# fish_V1_1.net
KiCad netlist of a schematic drawn in Altium Designer
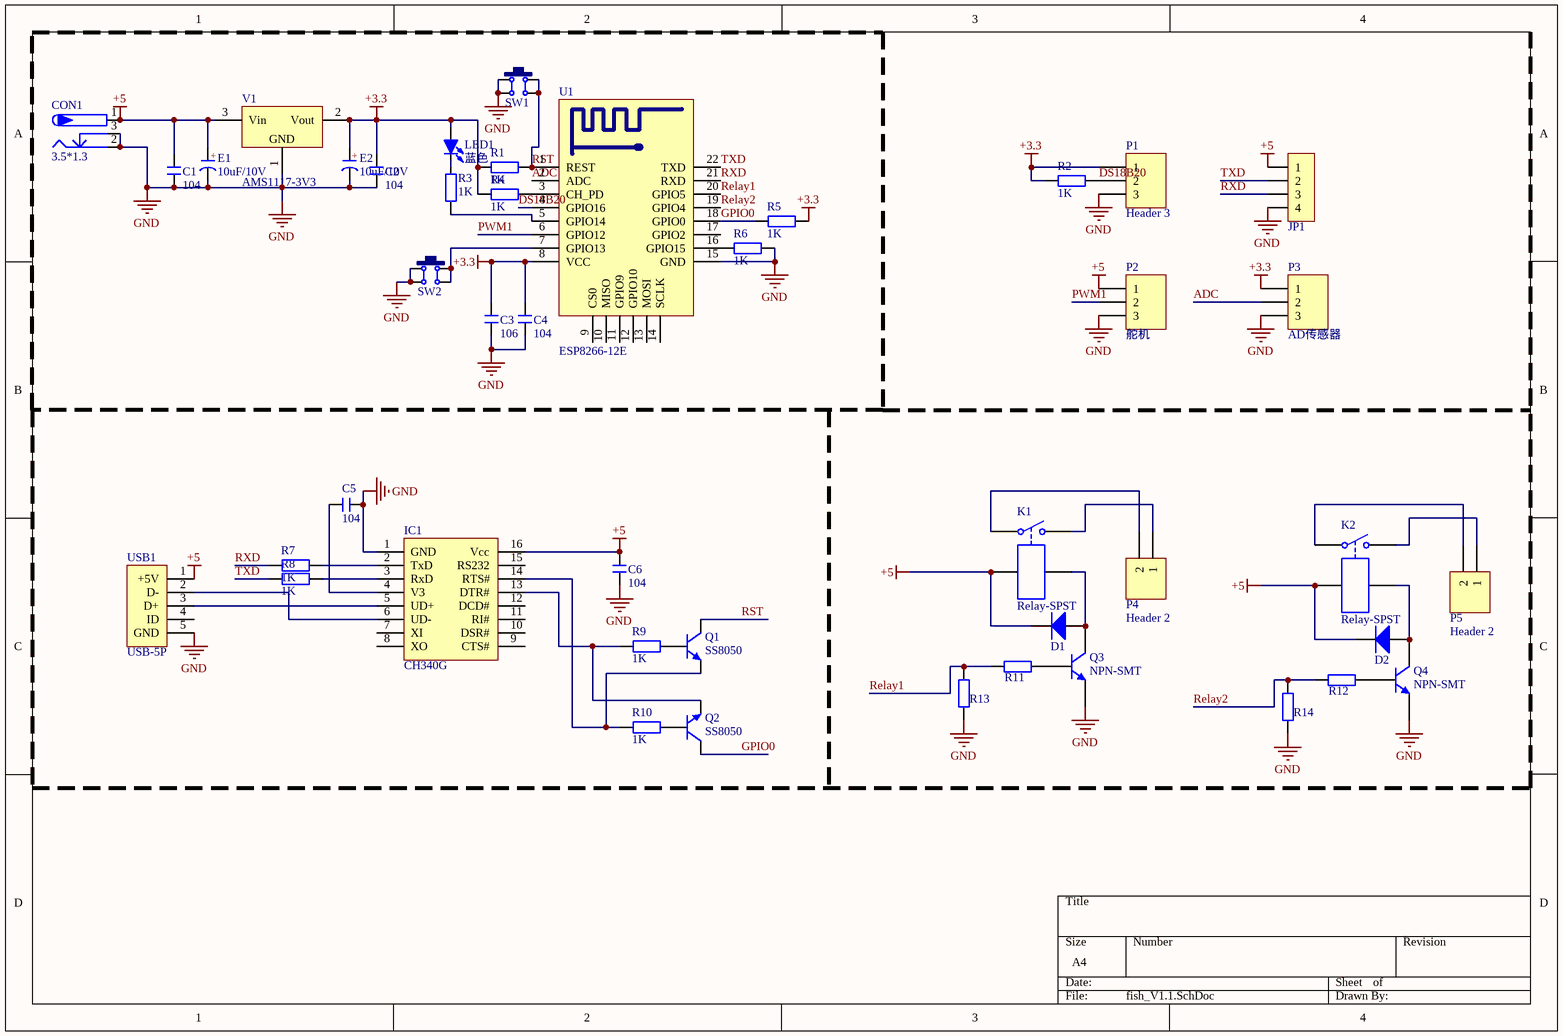
[diagram p0: fish_V1.1.SchDoc]

(export (version "E")
  (design (tool "Eeschema 10.0.6"))
  (components
    (comp (ref "C1")
      (value "104")
      (footprint "C 0603")
      (description "无极性贴片电容")
      (fields (field (name "版权归属") "黎明电子style"))
      (libsource (lib "电阻-电容-电感") (part "C"))
    )
    (comp (ref "C2")
      (value "104")
      (footprint "C 0603")
      (description "无极性贴片电容")
      (fields (field (name "版权归属") "黎明电子style"))
      (libsource (lib "电阻-电容-电感") (part "C"))
    )
    (comp (ref "C3")
      (value "106")
      (footprint "C 0603")
      (description "无极性贴片电容")
      (fields (field (name "版权归属") "黎明电子style"))
      (libsource (lib "电阻-电容-电感") (part "C"))
    )
    (comp (ref "C4")
      (value "104")
      (footprint "C 0603")
      (description "无极性贴片电容")
      (fields (field (name "版权归属") "黎明电子style"))
      (libsource (lib "电阻-电容-电感") (part "C"))
    )
    (comp (ref "C5")
      (value "104")
      (footprint "C 0603")
      (description "无极性贴片电容")
      (fields (field (name "版权归属") "黎明电子style"))
      (libsource (lib "电阻-电容-电感") (part "C"))
    )
    (comp (ref "C6")
      (value "104")
      (footprint "C 0603")
      (description "无极性贴片电容")
      (fields (field (name "版权归属") "黎明电子style"))
      (libsource (lib "电阻-电容-电感") (part "C"))
    )
    (comp (ref "CON1")
      (value "3.5*1.3")
      (footprint "DC-005")
      (description "低压电源接口")
      (fields (field (name "版权归属") "黎明电子style"))
      (libsource (lib "接口类") (part "P-DC"))
    )
    (comp (ref "D1")
      (value "Diode  Glass")
      (footprint "DSO-C2/X2.3")
      (description "High Conductance Fast Diode")
      (fields (field (name "PUBLISHER") "Altium Limited"))
      (libsource (lib "(NEW)DRC_MD Library") (part "Diode  Glass"))
    )
    (comp (ref "D2")
      (value "Diode  Glass")
      (footprint "DSO-C2/X2.3")
      (description "High Conductance Fast Diode")
      (fields (field (name "PUBLISHER") "Altium Limited"))
      (libsource (lib "(NEW)DRC_MD Library") (part "Diode  Glass"))
    )
    (comp (ref "E1")
      (value "10uF/10V")
      (footprint "CM D(6.3*5.4)")
      (description "贴片电解电容")
      (fields (field (name "版权归属") "黎明电子style"))
      (libsource (lib "电阻-电容-电感") (part "C-CM"))
    )
    (comp (ref "E2")
      (value "10uF/10V")
      (footprint "CM D(6.3*5.4)")
      (description "贴片电解电容")
      (fields (field (name "版权归属") "黎明电子style"))
      (libsource (lib "电阻-电容-电感") (part "C-CM"))
    )
    (comp (ref "IC1")
      (value "CH340G")
      (footprint "SOP16_L")
      (description "串口转USB")
      (fields (field (name "版权归属") "黎明电子style"))
      (libsource (lib "IC芯片") (part "CH340G"))
    )
    (comp (ref "JP1")
      (value "HDR-1X4")
      (footprint "XH2.54-4P")
      (description "4P接插件")
      (fields (field (name "版权归属") "黎明电子style"))
      (libsource (lib "接插件") (part "Header 4"))
    )
    (comp (ref "K1")
      (value "Relay-SPST")
      (footprint "RELAY_HF46F")
      (description "Single-Pole Single-Throw Relay")
      (fields (field (name "PUBLISHER") "Altium Limited"))
      (libsource (lib "(NEW)DRC_MD Library") (part "Relay-SPST"))
    )
    (comp (ref "K2")
      (value "Relay-SPST")
      (footprint "RELAY_HF46F")
      (description "Single-Pole Single-Throw Relay")
      (fields (field (name "PUBLISHER") "Altium Limited"))
      (libsource (lib "(NEW)DRC_MD Library") (part "Relay-SPST"))
    )
    (comp (ref "LED1")
      (value "蓝色")
      (footprint "LED 3MM-B")
      (description "插件LED")
      (fields (field (name "版权归属") "黎明电子style"))
      (libsource (lib "LED") (part "LED-3MM"))
    )
    (comp (ref "P1")
      (value "Header 3")
      (footprint "HX2.54-3")
      (description "Header, 3-Pin")
      (fields (field (name "PUBLISHER") "Altium Limited"))
      (libsource (lib "(NEW)DRC_MD Library") (part "Header 3"))
    )
    (comp (ref "P2")
      (value "舵机")
      (footprint "HX2.54-3")
      (description "Header, 3-Pin")
      (fields (field (name "PUBLISHER") "Altium Limited"))
      (libsource (lib "(NEW)DRC_MD Library") (part "Header 3"))
    )
    (comp (ref "P3")
      (value "AD传感器")
      (footprint "HX2.54-3")
      (description "Header, 3-Pin")
      (fields (field (name "PUBLISHER") "Altium Limited"))
      (libsource (lib "(NEW)DRC_MD Library") (part "Header 3"))
    )
    (comp (ref "P4")
      (value "Header 2")
      (footprint "HX5.08-2L")
      (description "Header, 2-Pin")
      (fields (field (name "PUBLISHER") "Altium Limited"))
      (libsource (lib "(NEW)DRC_MD Library") (part "Header 2"))
    )
    (comp (ref "P5")
      (value "Header 2")
      (footprint "HX5.08-2L")
      (description "Header, 2-Pin")
      (fields (field (name "PUBLISHER") "Altium Limited"))
      (libsource (lib "(NEW)DRC_MD Library") (part "Header 2"))
    )
    (comp (ref "Q1")
      (value "SS8050")
      (footprint "SOT23-3N")
      (description "高频放大-NPN型")
      (fields (field (name "版权归属") "黎明电子style"))
      (libsource (lib "三极管") (part "8050-SMD"))
    )
    (comp (ref "Q2")
      (value "SS8050")
      (footprint "SOT23-3N")
      (description "高频放大-NPN型")
      (fields (field (name "版权归属") "黎明电子style"))
      (libsource (lib "三极管") (part "8050-SMD"))
    )
    (comp (ref "Q3")
      (value "NPN-SMT")
      (footprint "SOT-23")
      (description "NPN Bipolar Transistor")
      (fields (field (name "PUBLISHER") "Altium Limited"))
      (libsource (lib "(NEW)DRC_MD Library") (part "NPN-SMT"))
    )
    (comp (ref "Q4")
      (value "NPN-SMT")
      (footprint "SOT-23")
      (description "NPN Bipolar Transistor")
      (fields (field (name "PUBLISHER") "Altium Limited"))
      (libsource (lib "(NEW)DRC_MD Library") (part "NPN-SMT"))
    )
    (comp (ref "R1")
      (value "1K")
      (footprint "R 0603")
      (description "贴片电阻")
      (fields (field (name "版权归属") "黎明电子style"))
      (libsource (lib "电阻-电容-电感") (part "R"))
    )
    (comp (ref "R2")
      (value "1K")
      (footprint "R 0603")
      (description "贴片电阻")
      (fields (field (name "版权归属") "黎明电子style"))
      (libsource (lib "电阻-电容-电感") (part "R"))
    )
    (comp (ref "R3")
      (value "1K")
      (footprint "R 0603")
      (description "贴片电阻")
      (fields (field (name "版权归属") "黎明电子style"))
      (libsource (lib "电阻-电容-电感") (part "R"))
    )
    (comp (ref "R4")
      (value "1K")
      (footprint "R 0603")
      (description "贴片电阻")
      (fields (field (name "版权归属") "黎明电子style"))
      (libsource (lib "电阻-电容-电感") (part "R"))
    )
    (comp (ref "R5")
      (value "1K")
      (footprint "R 0603")
      (description "贴片电阻")
      (fields (field (name "版权归属") "黎明电子style"))
      (libsource (lib "电阻-电容-电感") (part "R"))
    )
    (comp (ref "R6")
      (value "1K")
      (footprint "R 0603")
      (description "贴片电阻")
      (fields (field (name "版权归属") "黎明电子style"))
      (libsource (lib "电阻-电容-电感") (part "R"))
    )
    (comp (ref "R7")
      (value "1K")
      (footprint "R 0603")
      (description "贴片电阻")
      (fields (field (name "版权归属") "黎明电子style"))
      (libsource (lib "电阻-电容-电感") (part "R"))
    )
    (comp (ref "R8")
      (value "1K")
      (footprint "R 0603")
      (description "贴片电阻")
      (fields (field (name "版权归属") "黎明电子style"))
      (libsource (lib "电阻-电容-电感") (part "R"))
    )
    (comp (ref "R9")
      (value "1K")
      (footprint "R 0603")
      (description "贴片电阻")
      (fields (field (name "版权归属") "黎明电子style"))
      (libsource (lib "电阻-电容-电感") (part "R"))
    )
    (comp (ref "R10")
      (value "1K")
      (footprint "R 0603")
      (description "贴片电阻")
      (fields (field (name "版权归属") "黎明电子style"))
      (libsource (lib "电阻-电容-电感") (part "R"))
    )
    (comp (ref "R11")
      (value "Resistor Chip")
      (footprint "RES_0603")
      (description "Resistor")
      (fields (field (name "PUBLISHER") "Altium Limited"))
      (libsource (lib "(NEW)DRC_MD Library") (part "Resistor Chip"))
    )
    (comp (ref "R12")
      (value "Resistor Chip")
      (footprint "RES_0603")
      (description "Resistor")
      (fields (field (name "PUBLISHER") "Altium Limited"))
      (libsource (lib "(NEW)DRC_MD Library") (part "Resistor Chip"))
    )
    (comp (ref "R13")
      (value "Resistor Chip")
      (footprint "RES_0603")
      (description "Resistor")
      (fields (field (name "PUBLISHER") "Altium Limited"))
      (libsource (lib "") (part "Resistor Chip_1"))
    )
    (comp (ref "R14")
      (value "Resistor Chip")
      (footprint "RES_0603")
      (description "Resistor")
      (fields (field (name "PUBLISHER") "Altium Limited"))
      (libsource (lib "") (part "Resistor Chip_1"))
    )
    (comp (ref "SW1")
      (value "6x6x5")
      (footprint "TSW SMD-6*6*4.3")
      (description "贴片6x6轻触开关")
      (fields (field (name "版权归属") "黎明电子style"))
      (libsource (lib "按键-开关") (part "TSW SMD-6x6"))
    )
    (comp (ref "SW2")
      (value "6x6x5")
      (footprint "TSW SMD-6*6*4.3")
      (description "贴片6x6轻触开关")
      (fields (field (name "版权归属") "黎明电子style"))
      (libsource (lib "按键-开关") (part "TSW SMD-6x6"))
    )
    (comp (ref "U1")
      (value "ESP8266-12E")
      (footprint "ESP_12E")
      (description "串口 WIFI模块，ESP-12E")
      (fields (field (name "版权归属") "黎明电子style"))
      (libsource (lib "模块") (part "ESP8266-12E"))
    )
    (comp (ref "USB1")
      (value "USB-5P")
      (footprint "USB-MICRO_D")
      (description "微型USB母座")
      (fields (field (name "版权归属") "黎明电子style"))
      (libsource (lib "接口类") (part "USB-5P"))
    )
    (comp (ref "V1")
      (value "AMS1117-3V3")
      (footprint "SOT223_L")
      (description "三端稳压芯片")
      (fields (field (name "版权归属") "黎明电子style"))
      (libsource (lib "IC芯片") (part "AMS1117"))
    )
  )
  (nets
    (net (code "1") (name "+3.3") (class "Default")
      (node (ref "C2") (pin "2") (pinfunction "2_2") (pintype "passive"))
      (node (ref "C3") (pin "2") (pinfunction "2_2") (pintype "passive"))
      (node (ref "C4") (pin "2") (pinfunction "2_2") (pintype "passive"))
      (node (ref "E2") (pin "1") (pinfunction "A_1") (pintype "passive"))
      (node (ref "LED1") (pin "1") (pinfunction "A_1") (pintype "passive"))
      (node (ref "P1") (pin "1") (pinfunction "1_1") (pintype "passive"))
      (node (ref "P3") (pin "1") (pinfunction "1_1") (pintype "passive"))
      (node (ref "R1") (pin "1") (pinfunction "1_1") (pintype "passive"))
      (node (ref "R2") (pin "1") (pinfunction "1_1") (pintype "passive"))
      (node (ref "R4") (pin "1") (pinfunction "1_1") (pintype "passive"))
      (node (ref "R5") (pin "2") (pinfunction "2_2") (pintype "passive"))
      (node (ref "U1") (pin "8") (pinfunction "VCC_8") (pintype "passive"))
      (node (ref "V1") (pin "2") (pinfunction "Vout_2") (pintype "passive"))
    )
    (net (code "2") (name "+5") (class "Default")
      (node (ref "C1") (pin "2") (pinfunction "2_2") (pintype "passive"))
      (node (ref "C6") (pin "2") (pinfunction "2_2") (pintype "passive"))
      (node (ref "CON1") (pin "1") (pintype "power_in"))
      (node (ref "D1") (pin "2") (pinfunction "K_2") (pintype "passive"))
      (node (ref "D2") (pin "2") (pinfunction "K_2") (pintype "passive"))
      (node (ref "E1") (pin "1") (pinfunction "A_1") (pintype "passive"))
      (node (ref "IC1") (pin "16") (pinfunction "Vcc_16") (pintype "passive"))
      (node (ref "JP1") (pin "1") (pinfunction "1_1") (pintype "passive"))
      (node (ref "K1") (pin "3") (pinfunction "3_3") (pintype "passive"))
      (node (ref "K2") (pin "3") (pinfunction "3_3") (pintype "passive"))
      (node (ref "P2") (pin "1") (pinfunction "1_1") (pintype "passive"))
      (node (ref "USB1") (pin "1") (pinfunction "+5V_1") (pintype "passive"))
      (node (ref "V1") (pin "3") (pinfunction "Vin_3") (pintype "passive"))
    )
    (net (code "3") (name "/ADC") (class "Default")
      (node (ref "P3") (pin "2") (pinfunction "2_2") (pintype "passive"))
      (node (ref "U1") (pin "2") (pinfunction "ADC_2") (pintype "passive"))
    )
    (net (code "4") (name "/DS18B20") (class "Default")
      (node (ref "P1") (pin "2") (pinfunction "2_2") (pintype "passive"))
      (node (ref "R2") (pin "2") (pinfunction "2_2") (pintype "passive"))
      (node (ref "U1") (pin "4") (pinfunction "GPIO16_4") (pintype "passive"))
    )
    (net (code "5") (name "/GPIO0") (class "Default")
      (node (ref "Q2") (pin "3") (pinfunction "C_3") (pintype "passive"))
      (node (ref "R5") (pin "1") (pinfunction "1_1") (pintype "passive"))
      (node (ref "U1") (pin "18") (pinfunction "GPIO0_18") (pintype "passive"))
    )
    (net (code "6") (name "/PWM1") (class "Default")
      (node (ref "P2") (pin "2") (pinfunction "2_2") (pintype "passive"))
      (node (ref "U1") (pin "6") (pinfunction "GPIO12_6") (pintype "passive"))
    )
    (net (code "7") (name "/RST") (class "Default")
      (node (ref "Q1") (pin "3") (pinfunction "C_3") (pintype "passive"))
      (node (ref "R1") (pin "2") (pinfunction "2_2") (pintype "passive"))
      (node (ref "SW1") (pin "2") (pinfunction "2_2") (pintype "passive"))
      (node (ref "SW1") (pin "3") (pinfunction "3_3") (pintype "passive"))
      (node (ref "U1") (pin "1") (pinfunction "REST_1") (pintype "passive"))
    )
    (net (code "8") (name "/RXD") (class "Default")
      (node (ref "JP1") (pin "3") (pinfunction "3_3") (pintype "passive"))
      (node (ref "R7") (pin "1") (pinfunction "1_1") (pintype "passive"))
      (node (ref "U1") (pin "21") (pinfunction "RXD_21") (pintype "passive"))
    )
    (net (code "9") (name "/Relay1") (class "Default")
      (node (ref "R11") (pin "2") (pinfunction "2_2") (pintype "passive"))
      (node (ref "R13") (pin "2") (pinfunction "2_2") (pintype "passive"))
      (node (ref "U1") (pin "20") (pinfunction "GPIO5_20") (pintype "passive"))
    )
    (net (code "10") (name "/Relay2") (class "Default")
      (node (ref "R12") (pin "2") (pinfunction "2_2") (pintype "passive"))
      (node (ref "R14") (pin "2") (pinfunction "2_2") (pintype "passive"))
      (node (ref "U1") (pin "19") (pinfunction "GPIO4_19") (pintype "passive"))
    )
    (net (code "11") (name "/TXD") (class "Default")
      (node (ref "JP1") (pin "2") (pinfunction "2_2") (pintype "passive"))
      (node (ref "R8") (pin "1") (pinfunction "1_1") (pintype "passive"))
      (node (ref "U1") (pin "22") (pinfunction "TXD_22") (pintype "passive"))
    )
    (net (code "12") (name "GND") (class "Default")
      (node (ref "C1") (pin "1") (pinfunction "1_1") (pintype "passive"))
      (node (ref "C2") (pin "1") (pinfunction "1_1") (pintype "passive"))
      (node (ref "C3") (pin "1") (pinfunction "1_1") (pintype "passive"))
      (node (ref "C4") (pin "1") (pinfunction "1_1") (pintype "passive"))
      (node (ref "C5") (pin "2") (pinfunction "2_2") (pintype "passive"))
      (node (ref "C6") (pin "1") (pinfunction "1_1") (pintype "passive"))
      (node (ref "CON1") (pin "2") (pintype "power_in"))
      (node (ref "CON1") (pin "3") (pintype "power_in"))
      (node (ref "E1") (pin "2") (pinfunction "K_2") (pintype "passive"))
      (node (ref "E2") (pin "2") (pinfunction "K_2") (pintype "passive"))
      (node (ref "IC1") (pin "1") (pinfunction "GND_1") (pintype "passive"))
      (node (ref "JP1") (pin "4") (pinfunction "4_4") (pintype "passive"))
      (node (ref "P1") (pin "3") (pinfunction "3_3") (pintype "passive"))
      (node (ref "P2") (pin "3") (pinfunction "3_3") (pintype "passive"))
      (node (ref "P3") (pin "3") (pinfunction "3_3") (pintype "passive"))
      (node (ref "Q3") (pin "2") (pinfunction "E_2") (pintype "passive"))
      (node (ref "Q4") (pin "2") (pinfunction "E_2") (pintype "passive"))
      (node (ref "R13") (pin "1") (pinfunction "1_1") (pintype "passive"))
      (node (ref "R14") (pin "1") (pinfunction "1_1") (pintype "passive"))
      (node (ref "R6") (pin "2") (pinfunction "2_2") (pintype "passive"))
      (node (ref "SW1") (pin "1") (pinfunction "1_1") (pintype "passive"))
      (node (ref "SW1") (pin "4") (pinfunction "4_4") (pintype "passive"))
      (node (ref "SW2") (pin "1") (pinfunction "1_1") (pintype "passive"))
      (node (ref "SW2") (pin "4") (pinfunction "4_4") (pintype "passive"))
      (node (ref "U1") (pin "15") (pinfunction "GND_15") (pintype "passive"))
      (node (ref "USB1") (pin "5") (pinfunction "GND_5") (pintype "passive"))
      (node (ref "V1") (pin "1") (pinfunction "GND_1") (pintype "passive"))
    )
    (net (code "13") (name "Net-(D1-A)") (class "Default")
      (node (ref "D1") (pin "1") (pinfunction "A_1") (pintype "passive"))
      (node (ref "K1") (pin "4") (pinfunction "4_4") (pintype "passive"))
      (node (ref "Q3") (pin "3") (pinfunction "C_3") (pintype "passive"))
    )
    (net (code "14") (name "Net-(D2-A)") (class "Default")
      (node (ref "D2") (pin "1") (pinfunction "A_1") (pintype "passive"))
      (node (ref "K2") (pin "4") (pinfunction "4_4") (pintype "passive"))
      (node (ref "Q4") (pin "3") (pinfunction "C_3") (pintype "passive"))
    )
    (net (code "15") (name "Net-(IC1-DTR#)") (class "Default")
      (node (ref "IC1") (pin "13") (pinfunction "DTR#_13") (pintype "passive"))
      (node (ref "Q2") (pin "2") (pinfunction "E_2") (pintype "passive"))
      (node (ref "R9") (pin "1") (pinfunction "1_1") (pintype "passive"))
    )
    (net (code "16") (name "Net-(IC1-RTS#)") (class "Default")
      (node (ref "IC1") (pin "14") (pinfunction "RTS#_14") (pintype "passive"))
      (node (ref "Q1") (pin "2") (pinfunction "E_2") (pintype "passive"))
      (node (ref "R10") (pin "1") (pinfunction "1_1") (pintype "passive"))
    )
    (net (code "17") (name "Net-(IC1-RxD)") (class "Default")
      (node (ref "IC1") (pin "3") (pinfunction "RxD_3") (pintype "passive"))
      (node (ref "R8") (pin "2") (pinfunction "2_2") (pintype "passive"))
    )
    (net (code "18") (name "Net-(IC1-TxD)") (class "Default")
      (node (ref "IC1") (pin "2") (pinfunction "TxD_2") (pintype "passive"))
      (node (ref "R7") (pin "2") (pinfunction "2_2") (pintype "passive"))
    )
    (net (code "19") (name "Net-(IC1-UD+)") (class "Default")
      (node (ref "IC1") (pin "5") (pinfunction "UD+_5") (pintype "passive"))
      (node (ref "USB1") (pin "3") (pinfunction "D+_3") (pintype "passive"))
    )
    (net (code "20") (name "Net-(IC1-UD-)") (class "Default")
      (node (ref "IC1") (pin "6") (pinfunction "UD-_6") (pintype "passive"))
      (node (ref "USB1") (pin "2") (pinfunction "D-_2") (pintype "passive"))
    )
    (net (code "21") (name "Net-(IC1-V3)") (class "Default")
      (node (ref "C5") (pin "1") (pinfunction "1_1") (pintype "passive"))
      (node (ref "IC1") (pin "4") (pinfunction "V3_4") (pintype "passive"))
    )
    (net (code "22") (name "Net-(K1-Pad1)") (class "Default")
      (node (ref "K1") (pin "1") (pinfunction "1_1") (pintype "passive"))
      (node (ref "P4") (pin "2") (pinfunction "2_2") (pintype "passive"))
    )
    (net (code "23") (name "Net-(K1-Pad2)") (class "Default")
      (node (ref "K1") (pin "2") (pinfunction "2_2") (pintype "passive"))
      (node (ref "P4") (pin "1") (pinfunction "1_1") (pintype "passive"))
    )
    (net (code "24") (name "Net-(K2-Pad1)") (class "Default")
      (node (ref "K2") (pin "1") (pinfunction "1_1") (pintype "passive"))
      (node (ref "P5") (pin "2") (pinfunction "2_2") (pintype "passive"))
    )
    (net (code "25") (name "Net-(K2-Pad2)") (class "Default")
      (node (ref "K2") (pin "2") (pinfunction "2_2") (pintype "passive"))
      (node (ref "P5") (pin "1") (pinfunction "1_1") (pintype "passive"))
    )
    (net (code "26") (name "Net-(LED1-K)") (class "Default")
      (node (ref "LED1") (pin "2") (pinfunction "K_2") (pintype "passive"))
      (node (ref "R3") (pin "2") (pinfunction "2_2") (pintype "passive"))
    )
    (net (code "27") (name "Net-(Q1-B)") (class "Default")
      (node (ref "Q1") (pin "1") (pinfunction "B_1") (pintype "passive"))
      (node (ref "R9") (pin "2") (pinfunction "2_2") (pintype "passive"))
    )
    (net (code "28") (name "Net-(Q2-B)") (class "Default")
      (node (ref "Q2") (pin "1") (pinfunction "B_1") (pintype "passive"))
      (node (ref "R10") (pin "2") (pinfunction "2_2") (pintype "passive"))
    )
    (net (code "29") (name "Net-(Q3-B)") (class "Default")
      (node (ref "Q3") (pin "1") (pinfunction "B_1") (pintype "passive"))
      (node (ref "R11") (pin "1") (pinfunction "1_1") (pintype "passive"))
    )
    (net (code "30") (name "Net-(Q4-B)") (class "Default")
      (node (ref "Q4") (pin "1") (pinfunction "B_1") (pintype "passive"))
      (node (ref "R12") (pin "1") (pinfunction "1_1") (pintype "passive"))
    )
    (net (code "31") (name "Net-(U1-CH_PD)") (class "Default")
      (node (ref "R4") (pin "2") (pinfunction "2_2") (pintype "passive"))
      (node (ref "U1") (pin "3") (pinfunction "CH_PD_3") (pintype "passive"))
    )
    (net (code "32") (name "Net-(U1-GPIO13)") (class "Default")
      (node (ref "SW2") (pin "2") (pinfunction "2_2") (pintype "passive"))
      (node (ref "SW2") (pin "3") (pinfunction "3_3") (pintype "passive"))
      (node (ref "U1") (pin "7") (pinfunction "GPIO13_7") (pintype "passive"))
    )
    (net (code "33") (name "Net-(U1-GPIO14)") (class "Default")
      (node (ref "R3") (pin "1") (pinfunction "1_1") (pintype "passive"))
      (node (ref "U1") (pin "5") (pinfunction "GPIO14_5") (pintype "passive"))
    )
    (net (code "34") (name "Net-(U1-GPIO15)") (class "Default")
      (node (ref "R6") (pin "1") (pinfunction "1_1") (pintype "passive"))
      (node (ref "U1") (pin "16") (pinfunction "GPIO15_16") (pintype "passive"))
    )
    (net (code "35") (name "unconnected-(IC1-CTS#-Pad9)") (class "Default")
      (node (ref "IC1") (pin "9") (pinfunction "CTS#_9") (pintype "passive"))
    )
    (net (code "36") (name "unconnected-(IC1-DCD#-Pad12)") (class "Default")
      (node (ref "IC1") (pin "12") (pinfunction "DCD#_12") (pintype "passive"))
    )
    (net (code "37") (name "unconnected-(IC1-DSR#-Pad10)") (class "Default")
      (node (ref "IC1") (pin "10") (pinfunction "DSR#_10") (pintype "passive"))
    )
    (net (code "38") (name "unconnected-(IC1-RI#-Pad11)") (class "Default")
      (node (ref "IC1") (pin "11") (pinfunction "RI#_11") (pintype "passive"))
    )
    (net (code "39") (name "unconnected-(IC1-RS232-Pad15)") (class "Default")
      (node (ref "IC1") (pin "15") (pinfunction "RS232_15") (pintype "passive"))
    )
    (net (code "40") (name "unconnected-(IC1-XI-Pad7)") (class "Default")
      (node (ref "IC1") (pin "7") (pinfunction "XI_7") (pintype "passive"))
    )
    (net (code "41") (name "unconnected-(IC1-XO-Pad8)") (class "Default")
      (node (ref "IC1") (pin "8") (pinfunction "XO_8") (pintype "passive"))
    )
    (net (code "42") (name "unconnected-(U1-CS0-Pad9)") (class "Default")
      (node (ref "U1") (pin "9") (pinfunction "CS0_9") (pintype "passive"))
    )
    (net (code "43") (name "unconnected-(U1-GPIO2-Pad17)") (class "Default")
      (node (ref "U1") (pin "17") (pinfunction "GPIO2_17") (pintype "passive"))
    )
    (net (code "44") (name "unconnected-(U1-GPIO9-Pad11)") (class "Default")
      (node (ref "U1") (pin "11") (pinfunction "GPIO9_11") (pintype "passive"))
    )
    (net (code "45") (name "unconnected-(U1-GPIO10-Pad12)") (class "Default")
      (node (ref "U1") (pin "12") (pinfunction "GPIO10_12") (pintype "passive"))
    )
    (net (code "46") (name "unconnected-(U1-MISO-Pad10)") (class "Default")
      (node (ref "U1") (pin "10") (pinfunction "MISO_10") (pintype "passive"))
    )
    (net (code "47") (name "unconnected-(U1-MOSI-Pad13)") (class "Default")
      (node (ref "U1") (pin "13") (pinfunction "MOSI_13") (pintype "passive"))
    )
    (net (code "48") (name "unconnected-(U1-SCLK-Pad14)") (class "Default")
      (node (ref "U1") (pin "14") (pinfunction "SCLK_14") (pintype "passive"))
    )
    (net (code "49") (name "unconnected-(USB1-ID-Pad4)") (class "Default")
      (node (ref "USB1") (pin "4") (pinfunction "ID_4") (pintype "passive"))
    )
  )
)
